# Pakfa.net
KiCad netlist of a schematic drawn in EAGLE
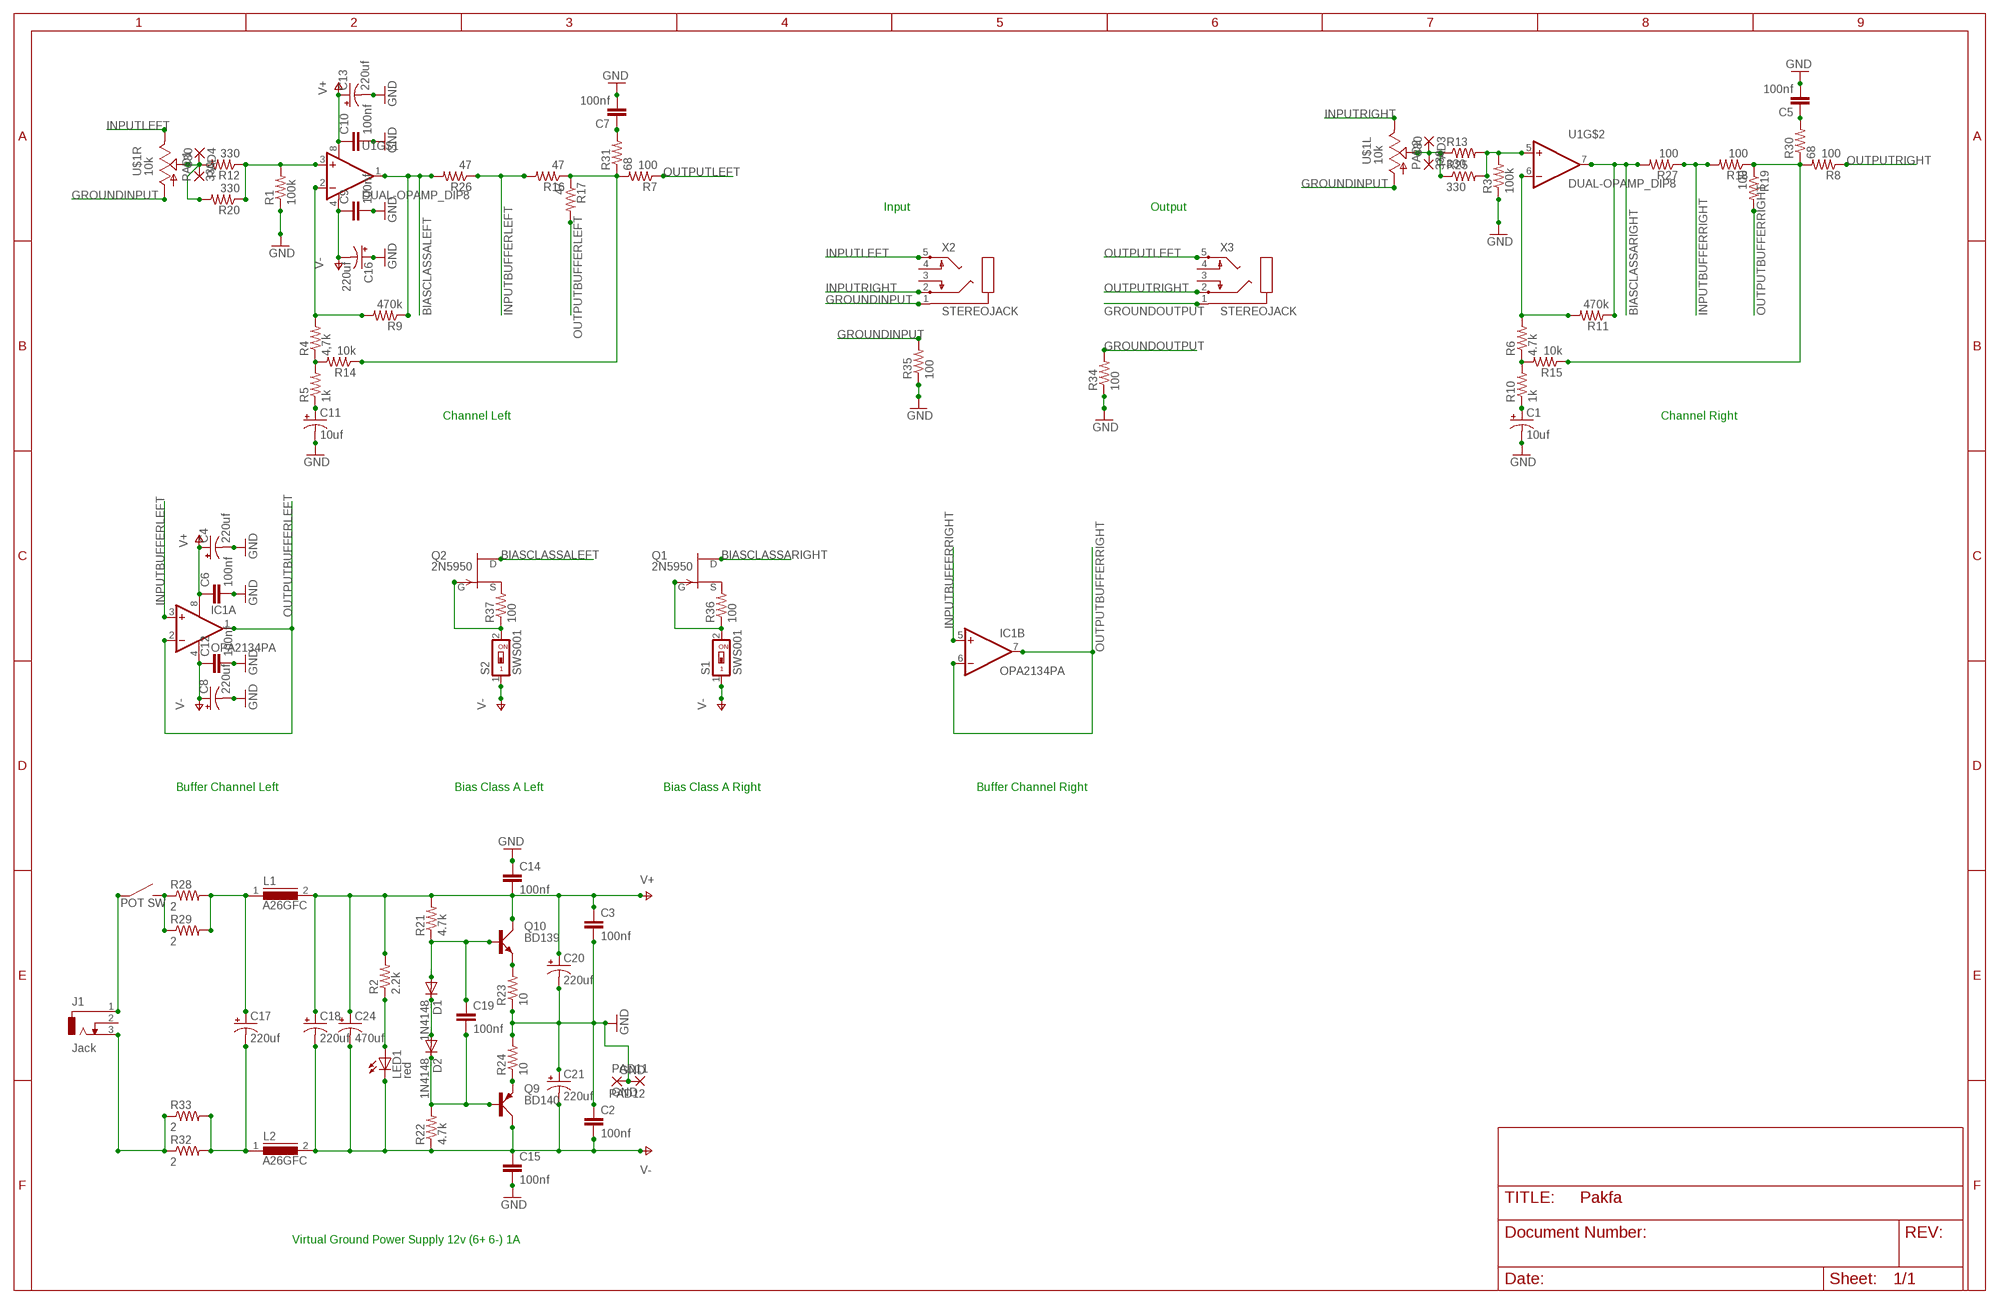
[diagram p0: schematic, sheet 1]

(export (version "E")
  (design (tool "Eeschema 10.0.6"))
  (components
    (comp (ref "C1")
      (value "10uf")
      (footprint "eagle-import:E5-10,5")
      (libsource (lib "eagle-import") (part "CPOL-USE5-10.5"))
    )
    (comp (ref "C2")
      (value "100nf")
      (footprint "eagle-import:C5B2.5")
      (libsource (lib "eagle-import") (part "C5/2.5"))
    )
    (comp (ref "C3")
      (value "100nf")
      (footprint "eagle-import:C5B2.5")
      (libsource (lib "eagle-import") (part "C5/2.5"))
    )
    (comp (ref "C4")
      (value "220uf")
      (footprint "eagle-import:E5-10,5")
      (libsource (lib "eagle-import") (part "CPOL-USE5-10.5"))
    )
    (comp (ref "C5")
      (value "100nf")
      (footprint "eagle-import:C5B2.5")
      (libsource (lib "eagle-import") (part "C5/2.5"))
    )
    (comp (ref "C6")
      (value "100nf")
      (footprint "eagle-import:C5B2.5")
      (libsource (lib "eagle-import") (part "C5/2.5"))
    )
    (comp (ref "C7")
      (value "100nf")
      (footprint "eagle-import:C5B2.5")
      (libsource (lib "eagle-import") (part "C5/2.5"))
    )
    (comp (ref "C8")
      (value "220uf")
      (footprint "eagle-import:E5-10,5")
      (libsource (lib "eagle-import") (part "CPOL-USE5-10.5"))
    )
    (comp (ref "C9")
      (value "100nf")
      (footprint "eagle-import:C5B2.5")
      (libsource (lib "eagle-import") (part "C5/2.5"))
    )
    (comp (ref "C10")
      (value "100nf")
      (footprint "eagle-import:C5B2.5")
      (libsource (lib "eagle-import") (part "C5/2.5"))
    )
    (comp (ref "C11")
      (value "10uf")
      (footprint "eagle-import:E5-10,5")
      (libsource (lib "eagle-import") (part "CPOL-USE5-10.5"))
    )
    (comp (ref "C12")
      (value "100nf")
      (footprint "eagle-import:C5B2.5")
      (libsource (lib "eagle-import") (part "C5/2.5"))
    )
    (comp (ref "C13")
      (value "220uf")
      (footprint "eagle-import:E5-10,5")
      (libsource (lib "eagle-import") (part "CPOL-USE5-10.5"))
    )
    (comp (ref "C14")
      (value "100nf")
      (footprint "eagle-import:C5B2.5")
      (libsource (lib "eagle-import") (part "C5/2.5"))
    )
    (comp (ref "C15")
      (value "100nf")
      (footprint "eagle-import:C5B2.5")
      (libsource (lib "eagle-import") (part "C5/2.5"))
    )
    (comp (ref "C16")
      (value "220uf")
      (footprint "eagle-import:E5-10,5")
      (libsource (lib "eagle-import") (part "CPOL-USE5-10.5"))
    )
    (comp (ref "C17")
      (value "220uf")
      (footprint "eagle-import:E2,5-7")
      (libsource (lib "eagle-import") (part "CPOL-USE2.5-7"))
    )
    (comp (ref "C18")
      (value "220uf")
      (footprint "eagle-import:E2,5-7")
      (libsource (lib "eagle-import") (part "CPOL-USE2.5-7"))
    )
    (comp (ref "C19")
      (value "100nf")
      (footprint "eagle-import:C5B2.5")
      (libsource (lib "eagle-import") (part "C5/2.5"))
    )
    (comp (ref "C20")
      (value "220uf")
      (footprint "eagle-import:E2,5-7")
      (libsource (lib "eagle-import") (part "CPOL-USE2.5-7"))
    )
    (comp (ref "C21")
      (value "220uf")
      (footprint "eagle-import:E2,5-7")
      (libsource (lib "eagle-import") (part "CPOL-USE2.5-7"))
    )
    (comp (ref "C24")
      (value "470uf")
      (footprint "eagle-import:E5-10,5")
      (libsource (lib "eagle-import") (part "CPOL-USE5-10.5"))
    )
    (comp (ref "D1")
      (value "1N4148")
      (footprint "eagle-import:DO35-7")
      (libsource (lib "eagle-import") (part "1N4148DO35-7"))
    )
    (comp (ref "D2")
      (value "1N4148")
      (footprint "eagle-import:DO35-7")
      (libsource (lib "eagle-import") (part "1N4148DO35-7"))
    )
    (comp (ref "IC1")
      (value "OPA2134PA")
      (footprint "eagle-import:DIL08")
      (libsource (lib "eagle-import") (part "OPA2PA134"))
    )
    (comp (ref "J1")
      (value "Jack")
      (footprint "eagle-import:DCJ0303")
      (libsource (lib "eagle-import") (part "DCJ0303"))
    )
    (comp (ref "L1")
      (value "A26GFC")
      (footprint "eagle-import:A26GFC")
      (libsource (lib "eagle-import") (part "A26GFC"))
    )
    (comp (ref "L2")
      (value "A26GFC")
      (footprint "eagle-import:A26GFC")
      (libsource (lib "eagle-import") (part "A26GFC"))
    )
    (comp (ref "LED1")
      (value "red")
      (footprint "eagle-import:LED3MM")
      (libsource (lib "eagle-import") (part "LED3MM"))
    )
    (comp (ref "PAD1")
      (value "330")
      (footprint "eagle-import:1,6_0,9")
      (libsource (lib "eagle-import") (part "1,6/0,9"))
    )
    (comp (ref "PAD2")
      (value "330")
      (footprint "eagle-import:1,6_0,9")
      (libsource (lib "eagle-import") (part "1,6/0,9"))
    )
    (comp (ref "PAD3")
      (value "330")
      (footprint "eagle-import:1,6_0,9")
      (libsource (lib "eagle-import") (part "1,6/0,9"))
    )
    (comp (ref "PAD4")
      (value "330")
      (footprint "eagle-import:1,6_0,9")
      (libsource (lib "eagle-import") (part "1,6/0,9"))
    )
    (comp (ref "PAD11")
      (value "GND")
      (footprint "eagle-import:1,6_0,9")
      (libsource (lib "eagle-import") (part "1,6/0,9"))
    )
    (comp (ref "PAD12")
      (value "GND")
      (footprint "eagle-import:1,6_0,9")
      (libsource (lib "eagle-import") (part "1,6/0,9"))
    )
    (comp (ref "Q1")
      (value "2N5950")
      (footprint "eagle-import:TO-92")
      (libsource (lib "eagle-import") (part "2N5950"))
    )
    (comp (ref "Q2")
      (value "2N5950")
      (footprint "eagle-import:TO-92")
      (libsource (lib "eagle-import") (part "2N5950"))
    )
    (comp (ref "Q9")
      (value "BD140")
      (footprint "eagle-import:TO126AV")
      (libsource (lib "eagle-import") (part "BD140"))
    )
    (comp (ref "Q10")
      (value "BD139")
      (footprint "eagle-import:TO126AV")
      (libsource (lib "eagle-import") (part "BD139"))
    )
    (comp (ref "R1")
      (value "100k")
      (footprint "eagle-import:0207_10")
      (libsource (lib "eagle-import") (part "R-US_0207/10"))
    )
    (comp (ref "R2")
      (value "2.2k")
      (footprint "eagle-import:0207_10")
      (libsource (lib "eagle-import") (part "resistor_348_R-US_0207/10"))
    )
    (comp (ref "R3")
      (value "100k")
      (footprint "eagle-import:0207_10")
      (libsource (lib "eagle-import") (part "R-US_0207/10"))
    )
    (comp (ref "R4")
      (value "4,7k")
      (footprint "eagle-import:0207_10")
      (libsource (lib "eagle-import") (part "R-US_0207/10"))
    )
    (comp (ref "R5")
      (value "1k")
      (footprint "eagle-import:0207_10")
      (libsource (lib "eagle-import") (part "R-US_0207/10"))
    )
    (comp (ref "R6")
      (value "4.7k")
      (footprint "eagle-import:0207_10")
      (libsource (lib "eagle-import") (part "R-US_0207/10"))
    )
    (comp (ref "R7")
      (value "100")
      (footprint "eagle-import:0207_12")
      (libsource (lib "eagle-import") (part "resistor_348_R-US_0207/12"))
    )
    (comp (ref "R8")
      (value "100")
      (footprint "eagle-import:0207_12")
      (libsource (lib "eagle-import") (part "resistor_348_R-US_0207/12"))
    )
    (comp (ref "R9")
      (value "470k")
      (footprint "eagle-import:0207_10")
      (libsource (lib "eagle-import") (part "R-US_0207/10"))
    )
    (comp (ref "R10")
      (value "1k")
      (footprint "eagle-import:0207_10")
      (libsource (lib "eagle-import") (part "R-US_0207/10"))
    )
    (comp (ref "R11")
      (value "470k")
      (footprint "eagle-import:0207_10")
      (libsource (lib "eagle-import") (part "R-US_0207/10"))
    )
    (comp (ref "R12")
      (value "330")
      (footprint "eagle-import:0207_10")
      (libsource (lib "eagle-import") (part "R-US_0207/10"))
    )
    (comp (ref "R13")
      (value "330")
      (footprint "eagle-import:0207_10")
      (libsource (lib "eagle-import") (part "R-US_0207/10"))
    )
    (comp (ref "R14")
      (value "10k")
      (footprint "eagle-import:0207_12")
      (libsource (lib "eagle-import") (part "resistor_348_R-US_0207/12"))
    )
    (comp (ref "R15")
      (value "10k")
      (footprint "eagle-import:0207_12")
      (libsource (lib "eagle-import") (part "resistor_348_R-US_0207/12"))
    )
    (comp (ref "R16")
      (value "47")
      (footprint "eagle-import:0207_12")
      (libsource (lib "eagle-import") (part "resistor_348_R-US_0207/12"))
    )
    (comp (ref "R17")
      (value "47")
      (footprint "eagle-import:0207_12")
      (libsource (lib "eagle-import") (part "resistor_348_R-US_0207/12"))
    )
    (comp (ref "R18")
      (value "100")
      (footprint "eagle-import:0207_12")
      (libsource (lib "eagle-import") (part "resistor_348_R-US_0207/12"))
    )
    (comp (ref "R19")
      (value "100")
      (footprint "eagle-import:0207_12")
      (libsource (lib "eagle-import") (part "resistor_348_R-US_0207/12"))
    )
    (comp (ref "R20")
      (value "330")
      (footprint "eagle-import:0207_10")
      (libsource (lib "eagle-import") (part "R-US_0207/10"))
    )
    (comp (ref "R21")
      (value "4.7k")
      (footprint "eagle-import:0207_10")
      (libsource (lib "eagle-import") (part "resistor_348_R-US_0207/10"))
    )
    (comp (ref "R22")
      (value "4.7k")
      (footprint "eagle-import:0207_10")
      (libsource (lib "eagle-import") (part "resistor_348_R-US_0207/10"))
    )
    (comp (ref "R23")
      (value "10")
      (footprint "eagle-import:0207_10")
      (libsource (lib "eagle-import") (part "resistor_348_R-US_0207/10"))
    )
    (comp (ref "R24")
      (value "10")
      (footprint "eagle-import:0207_10")
      (libsource (lib "eagle-import") (part "resistor_348_R-US_0207/10"))
    )
    (comp (ref "R25")
      (value "330")
      (footprint "eagle-import:0207_10")
      (libsource (lib "eagle-import") (part "R-US_0207/10"))
    )
    (comp (ref "R26")
      (value "47")
      (footprint "eagle-import:0207_10")
      (libsource (lib "eagle-import") (part "resistor_348_R-US_0207/10"))
    )
    (comp (ref "R27")
      (value "100")
      (footprint "eagle-import:0207_10")
      (libsource (lib "eagle-import") (part "resistor_348_R-US_0207/10"))
    )
    (comp (ref "R28")
      (value "2")
      (footprint "eagle-import:0207_10")
      (libsource (lib "eagle-import") (part "resistor_348_R-US_0207/10"))
    )
    (comp (ref "R29")
      (value "2")
      (footprint "eagle-import:0207_10")
      (libsource (lib "eagle-import") (part "resistor_348_R-US_0207/10"))
    )
    (comp (ref "R30")
      (value "68")
      (footprint "eagle-import:0207_7")
      (libsource (lib "eagle-import") (part "R-US_0207/7"))
    )
    (comp (ref "R31")
      (value "68")
      (footprint "eagle-import:0207_7")
      (libsource (lib "eagle-import") (part "R-US_0207/7"))
    )
    (comp (ref "R32")
      (value "2")
      (footprint "eagle-import:0207_10")
      (libsource (lib "eagle-import") (part "resistor_348_R-US_0207/10"))
    )
    (comp (ref "R33")
      (value "2")
      (footprint "eagle-import:0207_10")
      (libsource (lib "eagle-import") (part "resistor_348_R-US_0207/10"))
    )
    (comp (ref "R34")
      (value "100")
      (footprint "eagle-import:0207_7")
      (libsource (lib "eagle-import") (part "R-US_0207/7"))
    )
    (comp (ref "R35")
      (value "100")
      (footprint "eagle-import:0207_7")
      (libsource (lib "eagle-import") (part "R-US_0207/7"))
    )
    (comp (ref "R36")
      (value "100")
      (footprint "eagle-import:0204_5")
      (libsource (lib "eagle-import") (part "resistor_348_R-US_0204/5"))
    )
    (comp (ref "R37")
      (value "100")
      (footprint "eagle-import:0204_5")
      (libsource (lib "eagle-import") (part "resistor_348_R-US_0204/5"))
    )
    (comp (ref "S1")
      (value "SWS001")
      (footprint "eagle-import:SMS-001")
      (libsource (lib "eagle-import") (part "SWS001"))
    )
    (comp (ref "S2")
      (value "SWS001")
      (footprint "eagle-import:SMS-001")
      (libsource (lib "eagle-import") (part "SWS001"))
    )
    (comp (ref "U$1")
      (value "10k")
      (footprint "eagle-import:ALPS_RK0971221Z0X")
      (libsource (lib "eagle-import") (part "ALPS_RK0971221Z05"))
    )
    (comp (ref "U1")
      (value "DUAL-OPAMP_DIP8")
      (footprint "eagle-import:DIP-8")
      (libsource (lib "eagle-import") (part "DUAL-OPAMP_DIP8"))
    )
    (comp (ref "X2")
      (value "STEREOJACK")
      (footprint "eagle-import:STX3100")
      (libsource (lib "eagle-import") (part "STEREOJACK"))
    )
    (comp (ref "X3")
      (value "STEREOJACK")
      (footprint "eagle-import:STX3100")
      (libsource (lib "eagle-import") (part "STEREOJACK"))
    )
  )
  (nets
    (net (code "1") (name "/BIASCLASSALEFT") (class "Default")
      (node (ref "Q2") (pin "3") (pinfunction "D_3") (pintype "passive"))
      (node (ref "R26") (pin "2") (pinfunction "2_2") (pintype "passive"))
      (node (ref "R9") (pin "1") (pinfunction "1_1") (pintype "passive"))
      (node (ref "U1") (pin "1") (pinfunction "OUT_1") (pintype "output"))
    )
    (net (code "2") (name "/BIASCLASSARIGHT") (class "Default")
      (node (ref "Q1") (pin "3") (pinfunction "D_3") (pintype "passive"))
      (node (ref "R11") (pin "1") (pinfunction "1_1") (pintype "passive"))
      (node (ref "R27") (pin "2") (pinfunction "2_2") (pintype "passive"))
      (node (ref "U1") (pin "7") (pinfunction "OUT_7") (pintype "output"))
    )
    (net (code "3") (name "/GROUNDINPUT") (class "Default")
      (node (ref "R35") (pin "2") (pinfunction "2_2") (pintype "passive"))
      (node (ref "U$1") (pin "G1") (pinfunction "1_G1") (pintype "passive"))
      (node (ref "U$1") (pin "G2") (pinfunction "1_G2") (pintype "passive"))
      (node (ref "X2") (pin "1") (pinfunction "1_1") (pintype "passive"))
    )
    (net (code "4") (name "/GROUNDOUTPUT") (class "Default")
      (node (ref "R34") (pin "2") (pinfunction "2_2") (pintype "passive"))
      (node (ref "X3") (pin "1") (pinfunction "1_1") (pintype "passive"))
    )
    (net (code "5") (name "/INPUTBUFFERLEFT") (class "Default")
      (node (ref "IC1") (pin "3") (pinfunction "+IN_3") (pintype "input"))
      (node (ref "R16") (pin "2") (pinfunction "2_2") (pintype "passive"))
      (node (ref "R26") (pin "1") (pinfunction "1_1") (pintype "passive"))
    )
    (net (code "6") (name "/INPUTBUFFERRIGHT") (class "Default")
      (node (ref "IC1") (pin "5") (pinfunction "+IN_5") (pintype "input"))
      (node (ref "R18") (pin "2") (pinfunction "2_2") (pintype "passive"))
      (node (ref "R27") (pin "1") (pinfunction "1_1") (pintype "passive"))
    )
    (net (code "7") (name "/INPUTLEFT") (class "Default")
      (node (ref "U$1") (pin "I2") (pinfunction "3_I2") (pintype "passive"))
      (node (ref "X2") (pin "5") (pinfunction "5_5") (pintype "passive"))
    )
    (net (code "8") (name "/INPUTRIGHT") (class "Default")
      (node (ref "U$1") (pin "I1") (pinfunction "3_I1") (pintype "passive"))
      (node (ref "X2") (pin "2") (pinfunction "2_2") (pintype "passive"))
    )
    (net (code "9") (name "/OUTPUTBUFFERLEFT") (class "Default")
      (node (ref "IC1") (pin "1") (pinfunction "OUT_1") (pintype "output"))
      (node (ref "IC1") (pin "2") (pinfunction "-IN_2") (pintype "input"))
      (node (ref "R17") (pin "2") (pinfunction "2_2") (pintype "passive"))
    )
    (net (code "10") (name "/OUTPUTBUFFERRIGHT") (class "Default")
      (node (ref "IC1") (pin "6") (pinfunction "-IN_6") (pintype "input"))
      (node (ref "IC1") (pin "7") (pinfunction "OUT_7") (pintype "output"))
      (node (ref "R19") (pin "2") (pinfunction "2_2") (pintype "passive"))
    )
    (net (code "11") (name "/OUTPUTLEFT") (class "Default")
      (node (ref "R7") (pin "1") (pinfunction "1_1") (pintype "passive"))
      (node (ref "X3") (pin "5") (pinfunction "5_5") (pintype "passive"))
    )
    (net (code "12") (name "/OUTPUTRIGHT") (class "Default")
      (node (ref "R8") (pin "1") (pinfunction "1_1") (pintype "passive"))
      (node (ref "X3") (pin "2") (pinfunction "2_2") (pintype "passive"))
    )
    (net (code "13") (name "GND") (class "Default")
      (node (ref "C1") (pin "-") (pinfunction "-_-") (pintype "passive"))
      (node (ref "C10") (pin "2") (pinfunction "2_2") (pintype "passive"))
      (node (ref "C11") (pin "-") (pinfunction "-_-") (pintype "passive"))
      (node (ref "C12") (pin "2") (pinfunction "2_2") (pintype "passive"))
      (node (ref "C13") (pin "-") (pinfunction "-_-") (pintype "passive"))
      (node (ref "C14") (pin "1") (pinfunction "1_1") (pintype "passive"))
      (node (ref "C15") (pin "2") (pinfunction "2_2") (pintype "passive"))
      (node (ref "C16") (pin "+") (pinfunction "+_+") (pintype "passive"))
      (node (ref "C2") (pin "1") (pinfunction "1_1") (pintype "passive"))
      (node (ref "C20") (pin "-") (pinfunction "-_-") (pintype "passive"))
      (node (ref "C21") (pin "+") (pinfunction "+_+") (pintype "passive"))
      (node (ref "C3") (pin "2") (pinfunction "2_2") (pintype "passive"))
      (node (ref "C4") (pin "-") (pinfunction "-_-") (pintype "passive"))
      (node (ref "C5") (pin "2") (pinfunction "2_2") (pintype "passive"))
      (node (ref "C6") (pin "2") (pinfunction "2_2") (pintype "passive"))
      (node (ref "C7") (pin "2") (pinfunction "2_2") (pintype "passive"))
      (node (ref "C8") (pin "-") (pinfunction "-_-") (pintype "passive"))
      (node (ref "C9") (pin "2") (pinfunction "2_2") (pintype "passive"))
      (node (ref "PAD11") (pin "1") (pinfunction "P_1") (pintype "passive"))
      (node (ref "PAD12") (pin "1") (pinfunction "P_1") (pintype "passive"))
      (node (ref "R1") (pin "1") (pinfunction "1_1") (pintype "passive"))
      (node (ref "R23") (pin "1") (pinfunction "1_1") (pintype "passive"))
      (node (ref "R24") (pin "2") (pinfunction "2_2") (pintype "passive"))
      (node (ref "R3") (pin "1") (pinfunction "1_1") (pintype "passive"))
      (node (ref "R34") (pin "1") (pinfunction "1_1") (pintype "passive"))
      (node (ref "R35") (pin "1") (pinfunction "1_1") (pintype "passive"))
    )
    (net (code "14") (name "Net-(C1-Pad+)") (class "Default")
      (node (ref "C1") (pin "+") (pinfunction "+_+") (pintype "passive"))
      (node (ref "R10") (pin "1") (pinfunction "1_1") (pintype "passive"))
    )
    (net (code "15") (name "Net-(C5-Pad1)") (class "Default")
      (node (ref "C5") (pin "1") (pinfunction "1_1") (pintype "passive"))
      (node (ref "R30") (pin "2") (pinfunction "2_2") (pintype "passive"))
    )
    (net (code "16") (name "Net-(C7-Pad1)") (class "Default")
      (node (ref "C7") (pin "1") (pinfunction "1_1") (pintype "passive"))
      (node (ref "R31") (pin "2") (pinfunction "2_2") (pintype "passive"))
    )
    (net (code "17") (name "Net-(C11-Pad+)") (class "Default")
      (node (ref "C11") (pin "+") (pinfunction "+_+") (pintype "passive"))
      (node (ref "R5") (pin "1") (pinfunction "1_1") (pintype "passive"))
    )
    (net (code "18") (name "Net-(C17-Pad+)") (class "Default")
      (node (ref "C17") (pin "+") (pinfunction "+_+") (pintype "passive"))
      (node (ref "L1") (pin "1") (pinfunction "1_1") (pintype "passive"))
      (node (ref "R28") (pin "2") (pinfunction "2_2") (pintype "passive"))
      (node (ref "R29") (pin "2") (pinfunction "2_2") (pintype "passive"))
    )
    (net (code "19") (name "Net-(C17-Pad-)") (class "Default")
      (node (ref "C17") (pin "-") (pinfunction "-_-") (pintype "passive"))
      (node (ref "L2") (pin "1") (pinfunction "1_1") (pintype "passive"))
      (node (ref "R32") (pin "2") (pinfunction "2_2") (pintype "passive"))
      (node (ref "R33") (pin "2") (pinfunction "2_2") (pintype "passive"))
    )
    (net (code "20") (name "Net-(C19-Pad1)") (class "Default")
      (node (ref "C19") (pin "1") (pinfunction "1_1") (pintype "passive"))
      (node (ref "D1") (pin "A") (pinfunction "A_A") (pintype "passive"))
      (node (ref "Q10") (pin "B") (pinfunction "B_B") (pintype "passive"))
      (node (ref "R21") (pin "1") (pinfunction "1_1") (pintype "passive"))
    )
    (net (code "21") (name "Net-(C19-Pad2)") (class "Default")
      (node (ref "C19") (pin "2") (pinfunction "2_2") (pintype "passive"))
      (node (ref "D2") (pin "C") (pinfunction "C_C") (pintype "passive"))
      (node (ref "Q9") (pin "B") (pinfunction "B_B") (pintype "passive"))
      (node (ref "R22") (pin "2") (pinfunction "2_2") (pintype "passive"))
    )
    (net (code "22") (name "Net-(D1-PadC)") (class "Default")
      (node (ref "D1") (pin "C") (pinfunction "C_C") (pintype "passive"))
      (node (ref "D2") (pin "A") (pinfunction "A_A") (pintype "passive"))
    )
    (net (code "23") (name "Net-(J1-Pad1)") (class "Default")
      (node (ref "J1") (pin "1") (pinfunction "1_1") (pintype "passive"))
      (node (ref "U$1") (pin "S1") (pinfunction "S1_S1") (pintype "power_in"))
    )
    (net (code "24") (name "Net-(J1-Pad3)") (class "Default")
      (node (ref "J1") (pin "3") (pinfunction "3_3") (pintype "passive"))
      (node (ref "R32") (pin "1") (pinfunction "1_1") (pintype "passive"))
      (node (ref "R33") (pin "1") (pinfunction "1_1") (pintype "passive"))
    )
    (net (code "25") (name "Net-(LED1-PadA)") (class "Default")
      (node (ref "LED1") (pin "A") (pinfunction "A_A") (pintype "passive"))
      (node (ref "R2") (pin "1") (pinfunction "1_1") (pintype "passive"))
    )
    (net (code "26") (name "Net-(PAD1-P)") (class "Default")
      (node (ref "PAD1") (pin "1") (pinfunction "P_1") (pintype "passive"))
      (node (ref "PAD4") (pin "1") (pinfunction "P_1") (pintype "passive"))
      (node (ref "R12") (pin "2") (pinfunction "2_2") (pintype "passive"))
      (node (ref "R20") (pin "2") (pinfunction "2_2") (pintype "passive"))
      (node (ref "U$1") (pin "O2") (pinfunction "2_O2") (pintype "passive"))
    )
    (net (code "27") (name "Net-(PAD2-P)") (class "Default")
      (node (ref "PAD2") (pin "1") (pinfunction "P_1") (pintype "passive"))
      (node (ref "PAD3") (pin "1") (pinfunction "P_1") (pintype "passive"))
      (node (ref "R13") (pin "1") (pinfunction "1_1") (pintype "passive"))
      (node (ref "R25") (pin "1") (pinfunction "1_1") (pintype "passive"))
      (node (ref "U$1") (pin "O1") (pinfunction "2_O1") (pintype "passive"))
    )
    (net (code "28") (name "Net-(Q1-G)") (class "Default")
      (node (ref "Q1") (pin "1") (pinfunction "G_1") (pintype "passive"))
      (node (ref "R36") (pin "1") (pinfunction "1_1") (pintype "passive"))
      (node (ref "S1") (pin "2") (pinfunction "2_2") (pintype "passive"))
    )
    (net (code "29") (name "Net-(Q1-S)") (class "Default")
      (node (ref "Q1") (pin "2") (pinfunction "S_2") (pintype "passive"))
      (node (ref "R36") (pin "2") (pinfunction "2_2") (pintype "passive"))
    )
    (net (code "30") (name "Net-(Q2-G)") (class "Default")
      (node (ref "Q2") (pin "1") (pinfunction "G_1") (pintype "passive"))
      (node (ref "R37") (pin "1") (pinfunction "1_1") (pintype "passive"))
      (node (ref "S2") (pin "2") (pinfunction "2_2") (pintype "passive"))
    )
    (net (code "31") (name "Net-(Q2-S)") (class "Default")
      (node (ref "Q2") (pin "2") (pinfunction "S_2") (pintype "passive"))
      (node (ref "R37") (pin "2") (pinfunction "2_2") (pintype "passive"))
    )
    (net (code "32") (name "Net-(Q9-PadE)") (class "Default")
      (node (ref "Q9") (pin "E") (pinfunction "E_E") (pintype "passive"))
      (node (ref "R24") (pin "1") (pinfunction "1_1") (pintype "passive"))
    )
    (net (code "33") (name "Net-(Q10-PadE)") (class "Default")
      (node (ref "Q10") (pin "E") (pinfunction "E_E") (pintype "passive"))
      (node (ref "R23") (pin "2") (pinfunction "2_2") (pintype "passive"))
    )
    (net (code "34") (name "Net-(R10-Pad2)") (class "Default")
      (node (ref "R10") (pin "2") (pinfunction "2_2") (pintype "passive"))
      (node (ref "R15") (pin "2") (pinfunction "2_2") (pintype "passive"))
      (node (ref "R6") (pin "1") (pinfunction "1_1") (pintype "passive"))
    )
    (net (code "35") (name "Net-(R14-Pad1)") (class "Default")
      (node (ref "R14") (pin "1") (pinfunction "1_1") (pintype "passive"))
      (node (ref "R16") (pin "1") (pinfunction "1_1") (pintype "passive"))
      (node (ref "R17") (pin "1") (pinfunction "1_1") (pintype "passive"))
      (node (ref "R31") (pin "1") (pinfunction "1_1") (pintype "passive"))
      (node (ref "R7") (pin "2") (pinfunction "2_2") (pintype "passive"))
    )
    (net (code "36") (name "Net-(R14-Pad2)") (class "Default")
      (node (ref "R14") (pin "2") (pinfunction "2_2") (pintype "passive"))
      (node (ref "R4") (pin "1") (pinfunction "1_1") (pintype "passive"))
      (node (ref "R5") (pin "2") (pinfunction "2_2") (pintype "passive"))
    )
    (net (code "37") (name "Net-(R15-Pad1)") (class "Default")
      (node (ref "R15") (pin "1") (pinfunction "1_1") (pintype "passive"))
      (node (ref "R18") (pin "1") (pinfunction "1_1") (pintype "passive"))
      (node (ref "R19") (pin "1") (pinfunction "1_1") (pintype "passive"))
      (node (ref "R30") (pin "1") (pinfunction "1_1") (pintype "passive"))
      (node (ref "R8") (pin "2") (pinfunction "2_2") (pintype "passive"))
    )
    (net (code "38") (name "Net-(R28-Pad1)") (class "Default")
      (node (ref "R28") (pin "1") (pinfunction "1_1") (pintype "passive"))
      (node (ref "R29") (pin "1") (pinfunction "1_1") (pintype "passive"))
      (node (ref "U$1") (pin "S2") (pinfunction "S2_S2") (pintype "power_in"))
    )
    (net (code "39") (name "Net-(U1A-+IN)") (class "Default")
      (node (ref "R1") (pin "2") (pinfunction "2_2") (pintype "passive"))
      (node (ref "R12") (pin "1") (pinfunction "1_1") (pintype "passive"))
      (node (ref "R20") (pin "1") (pinfunction "1_1") (pintype "passive"))
      (node (ref "U1") (pin "3") (pinfunction "+IN_3") (pintype "input"))
    )
    (net (code "40") (name "Net-(U1A--IN)") (class "Default")
      (node (ref "R4") (pin "2") (pinfunction "2_2") (pintype "passive"))
      (node (ref "R9") (pin "2") (pinfunction "2_2") (pintype "passive"))
      (node (ref "U1") (pin "2") (pinfunction "-IN_2") (pintype "input"))
    )
    (net (code "41") (name "Net-(U1B-+IN)") (class "Default")
      (node (ref "R13") (pin "2") (pinfunction "2_2") (pintype "passive"))
      (node (ref "R25") (pin "2") (pinfunction "2_2") (pintype "passive"))
      (node (ref "R3") (pin "2") (pinfunction "2_2") (pintype "passive"))
      (node (ref "U1") (pin "5") (pinfunction "+IN_5") (pintype "input"))
    )
    (net (code "42") (name "Net-(U1B--IN)") (class "Default")
      (node (ref "R11") (pin "2") (pinfunction "2_2") (pintype "passive"))
      (node (ref "R6") (pin "2") (pinfunction "2_2") (pintype "passive"))
      (node (ref "U1") (pin "6") (pinfunction "-IN_6") (pintype "input"))
    )
    (net (code "43") (name "V+") (class "Default")
      (node (ref "C10") (pin "1") (pinfunction "1_1") (pintype "passive"))
      (node (ref "C13") (pin "+") (pinfunction "+_+") (pintype "passive"))
      (node (ref "C14") (pin "2") (pinfunction "2_2") (pintype "passive"))
      (node (ref "C18") (pin "+") (pinfunction "+_+") (pintype "passive"))
      (node (ref "C20") (pin "+") (pinfunction "+_+") (pintype "passive"))
      (node (ref "C24") (pin "+") (pinfunction "+_+") (pintype "passive"))
      (node (ref "C3") (pin "1") (pinfunction "1_1") (pintype "passive"))
      (node (ref "C4") (pin "+") (pinfunction "+_+") (pintype "passive"))
      (node (ref "C6") (pin "1") (pinfunction "1_1") (pintype "passive"))
      (node (ref "IC1") (pin "8") (pinfunction "V+_8") (pintype "power_in"))
      (node (ref "L1") (pin "2") (pinfunction "2_2") (pintype "passive"))
      (node (ref "Q10") (pin "C") (pinfunction "C_C") (pintype "passive"))
      (node (ref "R2") (pin "2") (pinfunction "2_2") (pintype "passive"))
      (node (ref "R21") (pin "2") (pinfunction "2_2") (pintype "passive"))
      (node (ref "U1") (pin "8") (pinfunction "V+_8") (pintype "power_in"))
    )
    (net (code "44") (name "V-") (class "Default")
      (node (ref "C12") (pin "1") (pinfunction "1_1") (pintype "passive"))
      (node (ref "C15") (pin "1") (pinfunction "1_1") (pintype "passive"))
      (node (ref "C16") (pin "-") (pinfunction "-_-") (pintype "passive"))
      (node (ref "C18") (pin "-") (pinfunction "-_-") (pintype "passive"))
      (node (ref "C2") (pin "2") (pinfunction "2_2") (pintype "passive"))
      (node (ref "C21") (pin "-") (pinfunction "-_-") (pintype "passive"))
      (node (ref "C24") (pin "-") (pinfunction "-_-") (pintype "passive"))
      (node (ref "C8") (pin "+") (pinfunction "+_+") (pintype "passive"))
      (node (ref "C9") (pin "1") (pinfunction "1_1") (pintype "passive"))
      (node (ref "IC1") (pin "4") (pinfunction "V-_4") (pintype "power_in"))
      (node (ref "L2") (pin "2") (pinfunction "2_2") (pintype "passive"))
      (node (ref "LED1") (pin "K") (pinfunction "C_K") (pintype "passive"))
      (node (ref "Q9") (pin "C") (pinfunction "C_C") (pintype "passive"))
      (node (ref "R22") (pin "1") (pinfunction "1_1") (pintype "passive"))
      (node (ref "S1") (pin "1") (pinfunction "1_1") (pintype "passive"))
      (node (ref "S2") (pin "1") (pinfunction "1_1") (pintype "passive"))
      (node (ref "U1") (pin "4") (pinfunction "V-_4") (pintype "power_in"))
    )
    (net (code "45") (name "unconnected-(J1-Pad2)") (class "Default")
      (node (ref "J1") (pin "2") (pinfunction "2_2") (pintype "passive"))
    )
    (net (code "46") (name "unconnected-(X2-Pad3)") (class "Default")
      (node (ref "X2") (pin "3") (pinfunction "3_3") (pintype "passive"))
    )
    (net (code "47") (name "unconnected-(X2-Pad4)") (class "Default")
      (node (ref "X2") (pin "4") (pinfunction "4_4") (pintype "passive"))
    )
    (net (code "48") (name "unconnected-(X3-Pad3)") (class "Default")
      (node (ref "X3") (pin "3") (pinfunction "3_3") (pintype "passive"))
    )
    (net (code "49") (name "unconnected-(X3-Pad4)") (class "Default")
      (node (ref "X3") (pin "4") (pinfunction "4_4") (pintype "passive"))
    )
  )
)
